# 05_AUDIO.net
KiCad netlist of a schematic drawn in Altium Designer
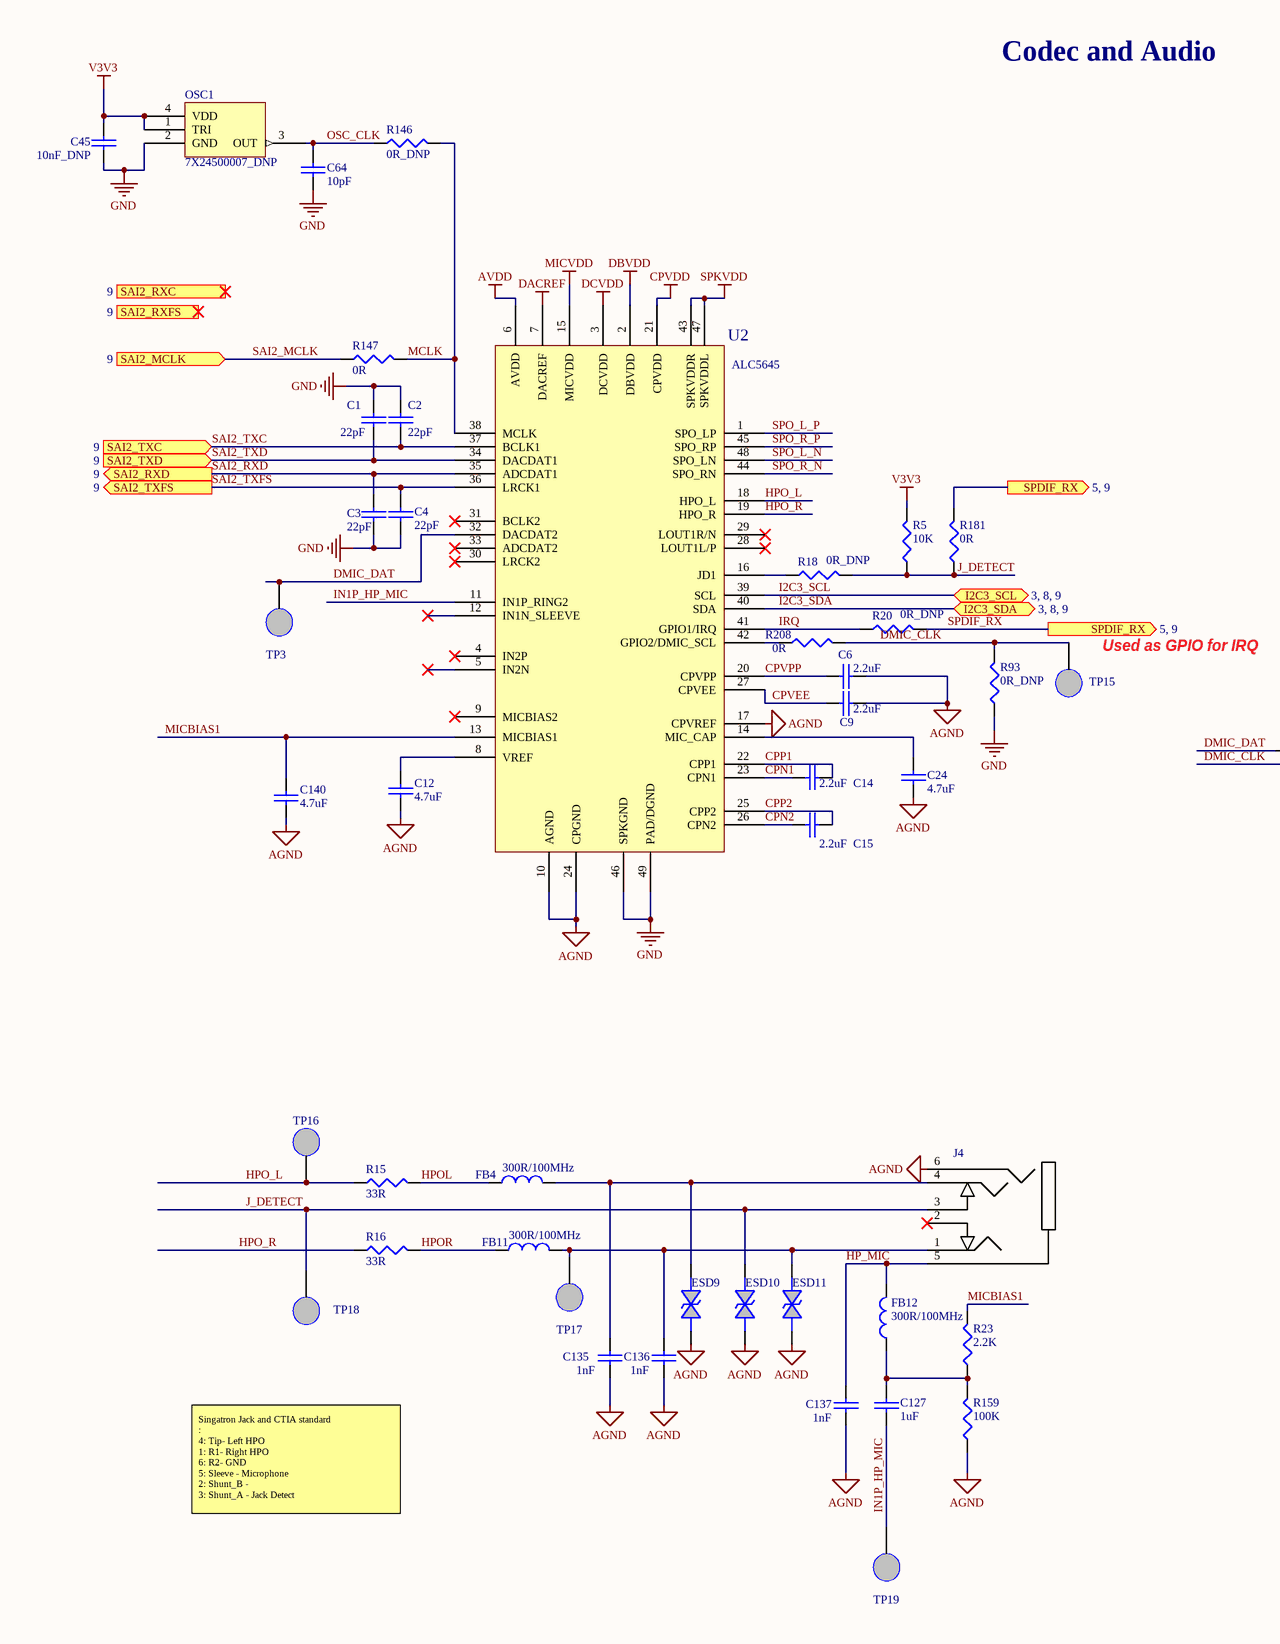
[diagram p0: 05_AUDIO.SchDoc, left]
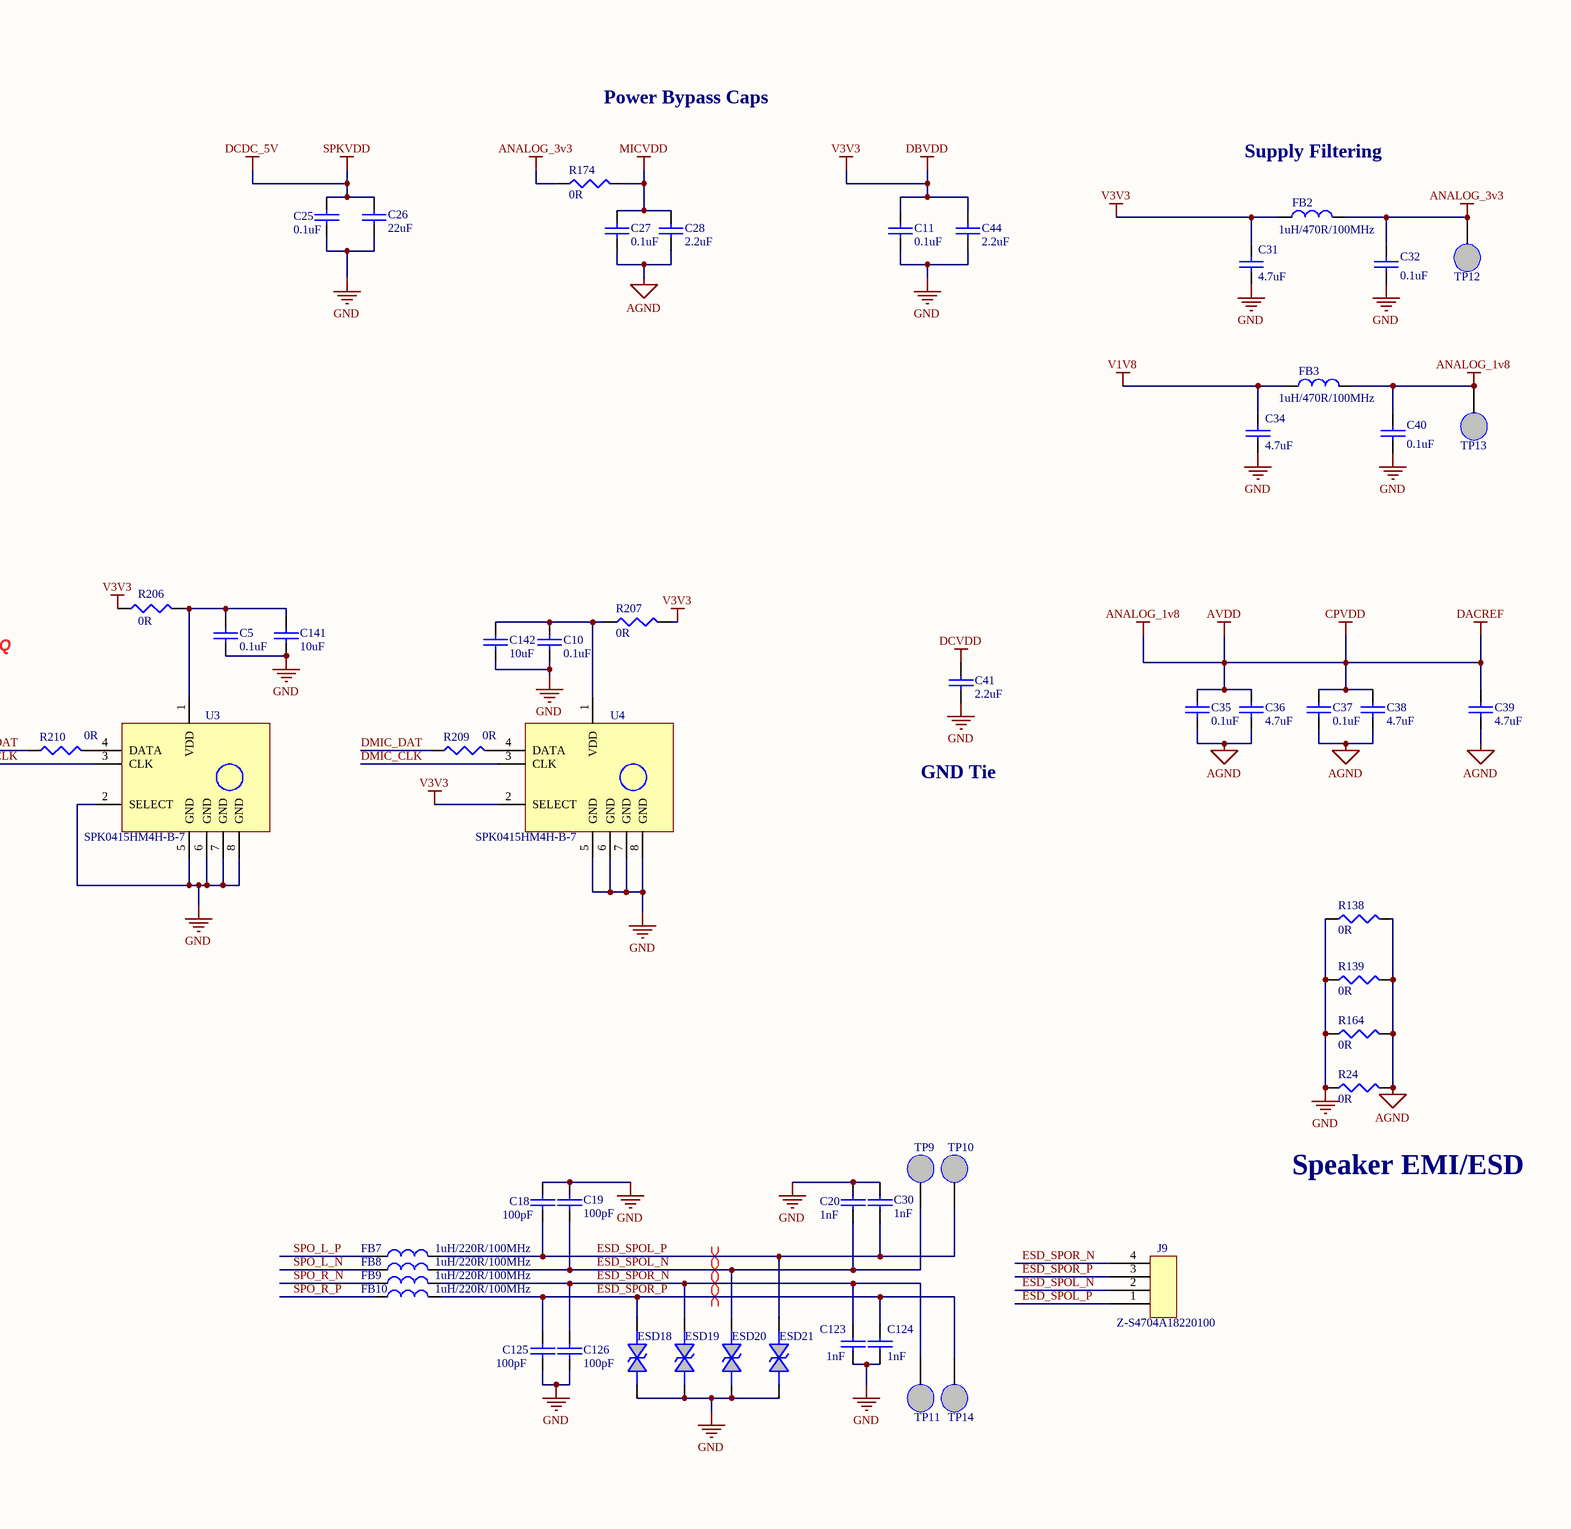
[diagram p1: 05_AUDIO.SchDoc, right]

(export (version "E")
  (design (tool "Eeschema 10.0.6"))
  (components
    (comp (ref "C1")
      (value "22pF")
      (footprint "0201")
      (description "CAP CER 22pF 6.3V 2% C0G NP0 0201")
      (fields (field (name "MPN") "GJM0335C0J220GB01D") (field (name "Comment") "22pF/6.3V"))
      (libsource (lib "links") (part "CAP_0201_22pF"))
    )
    (comp (ref "C2")
      (value "22pF")
      (footprint "0201")
      (description "CAP CER 22pF 6.3V 2% C0G NP0 0201")
      (fields (field (name "MPN") "GJM0335C0J220GB01D") (field (name "Comment") "22pF/6.3V"))
      (libsource (lib "links") (part "CAP_0201_22pF"))
    )
    (comp (ref "C3")
      (value "22pF")
      (footprint "0201")
      (description "CAP CER 22pF 6.3V 2% C0G NP0 0201")
      (fields (field (name "MPN") "GJM0335C0J220GB01D") (field (name "Comment") "22pF/6.3V"))
      (libsource (lib "links") (part "CAP_0201_22pF"))
    )
    (comp (ref "C4")
      (value "22pF")
      (footprint "0201")
      (description "CAP CER 22pF 6.3V 2% C0G NP0 0201")
      (fields (field (name "MPN") "GJM0335C0J220GB01D") (field (name "Comment") "22pF/6.3V"))
      (libsource (lib "links") (part "CAP_0201_22pF"))
    )
    (comp (ref "C5")
      (value "0.1uF")
      (footprint "0201")
      (description "CAP CER 0.1UF 10V 10% X5R 0201")
      (fields (field (name "MPN") "C0603X5R1A104K030BC") (field (name "Comment") "0.1uF/10V"))
      (libsource (lib "links") (part "CAP_0201_0.1uF"))
    )
    (comp (ref "C6")
      (value "2.2uF")
      (footprint "0201")
      (description "CAP CER 2.2uF 6.3V 20% X5R 0201")
      (fields (field (name "MPN") "GRM033R60J225ME15D") (field (name "Comment") "2.2uF/6.3V"))
      (libsource (lib "links") (part "CAP_0201_2.2uF"))
    )
    (comp (ref "C9")
      (value "2.2uF")
      (footprint "0201")
      (description "CAP CER 2.2uF 6.3V 20% X5R 0201")
      (fields (field (name "MPN") "GRM033R60J225ME15D") (field (name "Comment") "2.2uF/6.3V"))
      (libsource (lib "links") (part "CAP_0201_2.2uF"))
    )
    (comp (ref "C10")
      (value "0.1uF")
      (footprint "0201")
      (description "CAP CER 0.1UF 10V 10% X5R 0201")
      (fields (field (name "MPN") "C0603X5R1A104K030BC") (field (name "Comment") "0.1uF/10V"))
      (libsource (lib "links") (part "CAP_0201_0.1uF"))
    )
    (comp (ref "C11")
      (value "0.1uF")
      (footprint "0201")
      (description "CAP CER 0.1UF 10V 10% X5R 0201")
      (fields (field (name "MPN") "C0603X5R1A104K030BC") (field (name "Comment") "0.1uF/10V"))
      (libsource (lib "links") (part "CAP_0201_0.1uF"))
    )
    (comp (ref "C12")
      (value "4.7uF")
      (footprint "0402")
      (description "CAP CER 4.7UF 10V 20% X5R 0402")
      (fields (field (name "MPN") "C1005X5R1A475M050BC") (field (name "Comment") "4.7uF/10V"))
      (libsource (lib "links") (part "CAP_0201_4.7uF"))
    )
    (comp (ref "C14")
      (value "2.2uF")
      (footprint "0201")
      (description "CAP CER 2.2uF 6.3V 20% X5R 0201")
      (fields (field (name "MPN") "GRM033R60J225ME15D") (field (name "Comment") "2.2uF/6.3V"))
      (libsource (lib "links") (part "CAP_0201_2.2uF"))
    )
    (comp (ref "C15")
      (value "2.2uF")
      (footprint "0201")
      (description "CAP CER 2.2uF 6.3V 20% X5R 0201")
      (fields (field (name "MPN") "GRM033R60J225ME15D") (field (name "Comment") "2.2uF/6.3V"))
      (libsource (lib "links") (part "CAP_0201_2.2uF"))
    )
    (comp (ref "C18")
      (value "100pF")
      (footprint "0201")
      (description "CAP CER 100PF 25V X7R 0201")
      (fields (field (name "MPN") "GRM033R71E101KA01D") (field (name "Comment") "100pF/25V"))
      (libsource (lib "links") (part "CAP_0201_100pF"))
    )
    (comp (ref "C19")
      (value "100pF")
      (footprint "0201")
      (description "CAP CER 100PF 25V X7R 0201")
      (fields (field (name "MPN") "GRM033R71E101KA01D") (field (name "Comment") "100pF/25V"))
      (libsource (lib "links") (part "CAP_0201_100pF"))
    )
    (comp (ref "C20")
      (value "1nF")
      (footprint "0201")
      (description "CAP CER 1nF 25V 10% X7R 0201")
      (fields (field (name "MPN") "GRM033R71E102KA01D") (field (name "Comment") "1nF/25V"))
      (libsource (lib "links") (part "CAP_0201_1.0nF"))
    )
    (comp (ref "C24")
      (value "4.7uF")
      (footprint "0402")
      (description "CAP CER 4.7UF 10V 20% X5R 0402")
      (fields (field (name "MPN") "C1005X5R1A475M050BC") (field (name "Comment") "4.7uF/10V"))
      (libsource (lib "links") (part "CAP_0201_4.7uF"))
    )
    (comp (ref "C25")
      (value "0.1uF")
      (footprint "0402")
      (description "CAP CER 0.1uF 16V 10% X7R 0402")
      (fields (field (name "MPN") "C0402C104K4RACTU") (field (name "Comment") "0.1uF/16V"))
      (libsource (lib "links") (part "CAP_0402_0.1uF"))
    )
    (comp (ref "C26")
      (value "22uF")
      (footprint "0603")
      (description "CAP CER 22UF 6.3V 10% X5R 0603")
      (fields (field (name "MPN") "CL10A226KQ8NRNE") (field (name "Comment") "10uF/10V"))
      (libsource (lib "links") (part "CAP_0603_22uF"))
    )
    (comp (ref "C27")
      (value "0.1uF")
      (footprint "0201")
      (description "CAP CER 0.1UF 10V 10% X5R 0201")
      (fields (field (name "MPN") "C0603X5R1A104K030BC") (field (name "Comment") "0.1uF/10V"))
      (libsource (lib "links") (part "CAP_0201_0.1uF"))
    )
    (comp (ref "C28")
      (value "2.2uF")
      (footprint "0201")
      (description "CAP CER 2.2uF 6.3V 20% X5R 0201")
      (fields (field (name "MPN") "GRM033R60J225ME15D") (field (name "Comment") "2.2uF/6.3V"))
      (libsource (lib "links") (part "CAP_0201_2.2uF"))
    )
    (comp (ref "C30")
      (value "1nF")
      (footprint "0201")
      (description "CAP CER 1nF 25V 10% X7R 0201")
      (fields (field (name "MPN") "GRM033R71E102KA01D") (field (name "Comment") "1nF/25V"))
      (libsource (lib "links") (part "CAP_0201_1.0nF"))
    )
    (comp (ref "C31")
      (value "4.7uF")
      (footprint "0402")
      (description "CAP CER 4.7UF 10V 20% X5R 0402")
      (fields (field (name "MPN") "C1005X5R1A475M050BC") (field (name "Comment") "4.7uF/10V"))
      (libsource (lib "links") (part "CAP_0402_4.7uF"))
    )
    (comp (ref "C32")
      (value "0.1uF")
      (footprint "0603")
      (description "CAP CER 0.1UF 10V 10% X5R 0603")
      (fields (field (name "MPN") "GRM188R71C104M") (field (name "Comment") "0.1uF/10V"))
      (libsource (lib "links") (part "CAP_0603_0.1uF"))
    )
    (comp (ref "C34")
      (value "4.7uF")
      (footprint "0402")
      (description "CAP CER 4.7UF 10V 20% X5R 0402")
      (fields (field (name "MPN") "C1005X5R1A475M050BC") (field (name "Comment") "4.7uF/10V"))
      (libsource (lib "links") (part "CAP_0402_4.7uF"))
    )
    (comp (ref "C35")
      (value "0.1uF")
      (footprint "0201")
      (description "CAP CER 0.1UF 10V 10% X5R 0201")
      (fields (field (name "MPN") "C0603X5R1A104K030BC") (field (name "Comment") "0.1uF/10V"))
      (libsource (lib "links") (part "CAP_0201_0.1uF"))
    )
    (comp (ref "C36")
      (value "4.7uF")
      (footprint "0402")
      (description "CAP CER 4.7UF 10V 20% X5R 0402")
      (fields (field (name "MPN") "C1005X5R1A475M050BC") (field (name "Comment") "4.7uF/10V"))
      (libsource (lib "links") (part "CAP_0201_4.7uF"))
    )
    (comp (ref "C37")
      (value "0.1uF")
      (footprint "0201")
      (description "CAP CER 0.1UF 10V 10% X5R 0201")
      (fields (field (name "MPN") "C0603X5R1A104K030BC") (field (name "Comment") "0.1uF/10V"))
      (libsource (lib "links") (part "CAP_0201_0.1uF"))
    )
    (comp (ref "C38")
      (value "4.7uF")
      (footprint "0402")
      (description "CAP CER 4.7UF 10V 20% X5R 0402")
      (fields (field (name "MPN") "C1005X5R1A475M050BC") (field (name "Comment") "4.7uF/10V"))
      (libsource (lib "links") (part "CAP_0201_4.7uF"))
    )
    (comp (ref "C39")
      (value "4.7uF")
      (footprint "0402")
      (description "CAP CER 4.7UF 10V 20% X5R 0402")
      (fields (field (name "MPN") "C1005X5R1A475M050BC") (field (name "Comment") "4.7uF/10V"))
      (libsource (lib "links") (part "CAP_0201_4.7uF"))
    )
    (comp (ref "C40")
      (value "0.1uF")
      (footprint "0402")
      (description "CAP CER 0.1uF 16V 10% X7R 0402")
      (fields (field (name "MPN") "C0402C104K4RACTU") (field (name "Comment") "0.1uF/16V"))
      (libsource (lib "links") (part "CAP_0402_0.1uF"))
    )
    (comp (ref "C41")
      (value "2.2uF")
      (footprint "0201")
      (description "CAP CER 2.2uF 6.3V 20% X5R 0201")
      (fields (field (name "MPN") "GRM033R60J225ME15D") (field (name "Comment") "2.2uF/6.3V"))
      (libsource (lib "links") (part "CAP_0201_2.2uF"))
    )
    (comp (ref "C44")
      (value "2.2uF")
      (footprint "0201")
      (description "CAP CER 2.2uF 6.3V 20% X5R 0201")
      (fields (field (name "MPN") "GRM033R60J225ME15D") (field (name "Comment") "2.2uF/6.3V"))
      (libsource (lib "links") (part "CAP_0201_2.2uF"))
    )
    (comp (ref "C45")
      (value "10nF_DNP")
      (footprint "0201")
      (description "CAP CER 0.01UF 10V 10% X5R 0201")
      (fields (field (name "MPN") "GRM033R61A103KA01D"))
      (libsource (lib "links") (part "CAP_0201_10nF"))
    )
    (comp (ref "C64")
      (value "10pF")
      (footprint "0201")
      (description "CAP CER 10PF 25V 5% C0H 0201")
      (fields (field (name "MPN") "GJM0336C1E100JB01D") (field (name "Comment") "10pF/25V"))
      (libsource (lib "links") (part "CAP_0201_10pF_HF"))
    )
    (comp (ref "C123")
      (value "1nF")
      (footprint "0201")
      (description "CAP CER 1nF 25V 10% X7R 0201")
      (fields (field (name "MPN") "GRM033R71E102KA01D") (field (name "Comment") "1nF/25V"))
      (libsource (lib "links") (part "CAP_0201_1.0nF"))
    )
    (comp (ref "C124")
      (value "1nF")
      (footprint "0201")
      (description "CAP CER 1nF 25V 10% X7R 0201")
      (fields (field (name "MPN") "GRM033R71E102KA01D") (field (name "Comment") "1nF/25V"))
      (libsource (lib "links") (part "CAP_0201_1.0nF"))
    )
    (comp (ref "C125")
      (value "100pF")
      (footprint "0201")
      (description "CAP CER 100PF 25V X7R 0201")
      (fields (field (name "MPN") "GRM033R71E101KA01D") (field (name "Comment") "100pF/25V"))
      (libsource (lib "links") (part "CAP_0201_100pF"))
    )
    (comp (ref "C126")
      (value "100pF")
      (footprint "0201")
      (description "CAP CER 100PF 25V X7R 0201")
      (fields (field (name "MPN") "GRM033R71E101KA01D") (field (name "Comment") "100pF/25V"))
      (libsource (lib "links") (part "CAP_0201_100pF"))
    )
    (comp (ref "C127")
      (value "1uF")
      (footprint "0402")
      (description "CAP CER 1.0UF 6.3V 10% X5R 0402")
      (fields (field (name "MPN") "C0603X5R0J105M030BC") (field (name "Comment") "1uF/6.3V"))
      (libsource (lib "links") (part "CAP_0402_1.0uF"))
    )
    (comp (ref "C135")
      (value "1nF")
      (footprint "0201")
      (description "CAP CER 1nF 25V 10% X7R 0201")
      (fields (field (name "MPN") "GRM033R71E102KA01D") (field (name "Comment") "1nF/25V"))
      (libsource (lib "links") (part "CAP_0201_1.0nF"))
    )
    (comp (ref "C136")
      (value "1nF")
      (footprint "0201")
      (description "CAP CER 1nF 25V 10% X7R 0201")
      (fields (field (name "MPN") "GRM033R71E102KA01D") (field (name "Comment") "1nF/25V"))
      (libsource (lib "links") (part "CAP_0201_1.0nF"))
    )
    (comp (ref "C137")
      (value "1nF")
      (footprint "0201")
      (description "CAP CER 1nF 25V 10% X7R 0201")
      (fields (field (name "MPN") "GRM033R71E102KA01D") (field (name "Comment") "1nF/25V"))
      (libsource (lib "links") (part "CAP_0201_1.0nF"))
    )
    (comp (ref "C140")
      (value "4.7uF")
      (footprint "0402")
      (description "CAP CER 4.7UF 10V 20% X5R 0402")
      (fields (field (name "MPN") "C1005X5R1A475M050BC") (field (name "Comment") "4.7uF/10V"))
      (libsource (lib "links") (part "CAP_0201_4.7uF"))
    )
    (comp (ref "C141")
      (value "10uF")
      (footprint "0402")
      (description "CAP CER 10UF 10V 20% X5R 0402")
      (fields (field (name "MPN") "CL05A106MP5NUNC") (field (name "Comment") "10uF/10V"))
      (libsource (lib "links") (part "CAP_0402_10uF"))
    )
    (comp (ref "C142")
      (value "10uF")
      (footprint "0402")
      (description "CAP CER 10UF 10V 20% X5R 0402")
      (fields (field (name "MPN") "CL05A106MP5NUNC") (field (name "Comment") "10uF/10V"))
      (libsource (lib "links") (part "CAP_0402_10uF"))
    )
    (comp (ref "ESD9")
      (value "3.5pF/5V")
      (footprint "0201")
      (description "DIODE TVS 15kV 10V 50A 8pF SMT RoHS")
      (fields (field (name "MPN") "DESD5V0V1BCSP-7"))
      (libsource (lib "links") (part "DIODE BI-DIR TRIG"))
    )
    (comp (ref "ESD10")
      (value "3.5pF/5V")
      (footprint "0201")
      (description "DIODE TVS 15kV 10V 50A 8pF SMT RoHS")
      (fields (field (name "MPN") "DESD5V0V1BCSP-7"))
      (libsource (lib "links") (part "DIODE BI-DIR TRIG"))
    )
    (comp (ref "ESD11")
      (value "3.5pF/5V")
      (footprint "0201")
      (description "DIODE TVS 15kV 10V 50A 8pF SMT RoHS")
      (fields (field (name "MPN") "DESD5V0V1BCSP-7"))
      (libsource (lib "links") (part "DIODE BI-DIR TRIG"))
    )
    (comp (ref "ESD18")
      (value "3.5pF/5V")
      (footprint "0201")
      (description "DIODE TVS 15kV 10V 50A 8pF SMT RoHS")
      (fields (field (name "MPN") "DESD5V0V1BCSP-7"))
      (libsource (lib "links") (part "DIODE BI-DIR TRIG"))
    )
    (comp (ref "ESD19")
      (value "3.5pF/5V")
      (footprint "0201")
      (description "DIODE TVS 15kV 10V 50A 8pF SMT RoHS")
      (fields (field (name "MPN") "DESD5V0V1BCSP-7"))
      (libsource (lib "links") (part "DIODE BI-DIR TRIG"))
    )
    (comp (ref "ESD20")
      (value "3.5pF/5V")
      (footprint "0201")
      (description "DIODE TVS 15kV 10V 50A 8pF SMT RoHS")
      (fields (field (name "MPN") "DESD5V0V1BCSP-7"))
      (libsource (lib "links") (part "DIODE BI-DIR TRIG"))
    )
    (comp (ref "ESD21")
      (value "3.5pF/5V")
      (footprint "0201")
      (description "DIODE TVS 15kV 10V 50A 8pF SMT RoHS")
      (fields (field (name "MPN") "DESD5V0V1BCSP-7"))
      (libsource (lib "links") (part "DIODE BI-DIR TRIG"))
    )
    (comp (ref "FB2")
      (value "1uH/470R/100MHz")
      (footprint "0603")
      (description "FERRITE CHIP 470 OHM 1.0A 0603")
      (fields (field (name "MPN") "BLM18PG471SN1"))
      (libsource (lib "SpacePark") (part "INDUCTOR_BLM18PG471SN1"))
    )
    (comp (ref "FB3")
      (value "1uH/470R/100MHz")
      (footprint "0603")
      (description "FERRITE CHIP 470 OHM 1.0A 0603")
      (fields (field (name "MPN") "BLM18PG471SN1"))
      (libsource (lib "SpacePark") (part "INDUCTOR_BLM18PG471SN1"))
    )
    (comp (ref "FB4")
      (value "300R/100MHz")
      (footprint "0402")
      (description "EMI FILTER FCM1005KF-301T03 (300,300MA)")
      (fields (field (name "MPN") "FCM1005KF-301T03"))
      (libsource (lib "SpacePark") (part "INDUCTOR_BLM18EG221SN1D"))
    )
    (comp (ref "FB7")
      (value "1uH/220R/100MHz")
      (footprint "0603")
      (description "FERRITE CHIP 220 OHM 2.0A 0603")
      (fields (field (name "MPN") "BLM18EG221SN1D"))
      (libsource (lib "SpacePark") (part "INDUCTOR_BLM18EG221SN1D"))
    )
    (comp (ref "FB8")
      (value "1uH/220R/100MHz")
      (footprint "0603")
      (description "FERRITE CHIP 220 OHM 2.0A 0603")
      (fields (field (name "MPN") "BLM18EG221SN1D"))
      (libsource (lib "SpacePark") (part "INDUCTOR_BLM18EG221SN1D"))
    )
    (comp (ref "FB9")
      (value "1uH/220R/100MHz")
      (footprint "0603")
      (description "FERRITE CHIP 220 OHM 2.0A 0603")
      (fields (field (name "MPN") "BLM18EG221SN1D"))
      (libsource (lib "SpacePark") (part "INDUCTOR_BLM18EG221SN1D"))
    )
    (comp (ref "FB10")
      (value "1uH/220R/100MHz")
      (footprint "0603")
      (description "FERRITE CHIP 220 OHM 2.0A 0603")
      (fields (field (name "MPN") "BLM18EG221SN1D"))
      (libsource (lib "SpacePark") (part "INDUCTOR_BLM18EG221SN1D"))
    )
    (comp (ref "FB11")
      (value "300R/100MHz")
      (footprint "0402")
      (description "EMI FILTER FCM1005KF-301T03 (300,300MA)")
      (fields (field (name "MPN") "FCM1005KF-301T03"))
      (libsource (lib "SpacePark") (part "INDUCTOR_BLM18EG221SN1D"))
    )
    (comp (ref "FB12")
      (value "300R/100MHz")
      (footprint "0402")
      (description "EMI FILTER FCM1005KF-301T03 (300,300MA)")
      (fields (field (name "MPN") "FCM1005KF-301T03"))
      (libsource (lib "SpacePark") (part "INDUCTOR_BLM18EG221SN1D"))
    )
    (comp (ref "J4")
      (value "CONN_2SJ2296-000111")
      (footprint "AUDIO-2SJ2296-000111")
      (description "CONN AUDIO JACK 3.5MM 6COND SMD")
      (fields (field (name "MPN") "2SJ2296-000111"))
      (libsource (lib "SpacePark") (part "CONN_2SJ2296-000111"))
    )
    (comp (ref "J9")
      (value "Z-S4704A18220100")
      (footprint "SIP4-2_54-S4704A18220100")
      (description "CONN TERM BLOCK 2.54MM 4POS PCB")
      (libsource (lib "SpacePark") (part "CONN_TERMINAL_4POS_PHOENIX"))
    )
    (comp (ref "OSC1")
      (value "7X24500007_DNP")
      (footprint "4-SMD-OSC")
      (description "24.576MHz SINE Oscillator Surface Mount 3.3V 13mA Enable/Disable")
      (libsource (lib "SpacePark") (part "OSC_7X24500007"))
    )
    (comp (ref "R5")
      (value "10K")
      (footprint "0201")
      (description "RES SMD 10K OHM JUMPER 1/20W  0201")
      (fields (field (name "MPN") "ERJ-1GEF103C"))
      (libsource (lib "links") (part "R_0201_10K"))
    )
    (comp (ref "R15")
      (value "33R")
      (footprint "0402")
      (description "RES SMD 33 OHM 1% 1/10W 0402")
      (fields (field (name "MPN") "RC0402FR-0733R"))
      (libsource (lib "links") (part "R_0402_33"))
    )
    (comp (ref "R16")
      (value "33R")
      (footprint "0402")
      (description "RES SMD 33 OHM 1% 1/10W 0402")
      (fields (field (name "MPN") "RC0402FR-0733R"))
      (libsource (lib "links") (part "R_0402_33"))
    )
    (comp (ref "R18")
      (value "0R_DNP")
      (footprint "0201")
      (description "RES SMD 0.0OHM JUMPER 1/20W 0201")
      (fields (field (name "MPN") "ERJ-1GN0R00C"))
      (libsource (lib "links") (part "R_0201_0"))
    )
    (comp (ref "R20")
      (value "0R_DNP")
      (footprint "0201")
      (description "RES SMD 0.0OHM JUMPER 1/20W 0201")
      (fields (field (name "MPN") "ERJ-1GN0R00C"))
      (libsource (lib "links") (part "R_0201_0"))
    )
    (comp (ref "R23")
      (value "2.2K")
      (footprint "0201")
      (description "RES SMD 2.2K OHM 1% 1/20W 0201")
      (fields (field (name "MPN") "ERJ-1GEF2201C"))
      (libsource (lib "links") (part "R_0201_2.2K"))
    )
    (comp (ref "R24")
      (value "0R")
      (footprint "0201")
      (description "RES SMD 0.0OHM JUMPER 1/20W 0201")
      (fields (field (name "MPN") "ERJ-1GN0R00C"))
      (libsource (lib "links") (part "R_0805_0"))
    )
    (comp (ref "R93")
      (value "0R_DNP")
      (footprint "0201")
      (description "RES SMD 0.0OHM JUMPER 1/20W 0201")
      (fields (field (name "MPN") "ERJ-1GN0R00C"))
      (libsource (lib "links") (part "R_0201_0"))
    )
    (comp (ref "R138")
      (value "0R")
      (footprint "0201")
      (description "RES SMD 0.0OHM JUMPER 1/20W 0201")
      (fields (field (name "MPN") "ERJ-1GN0R00C"))
      (libsource (lib "links") (part "R_0805_0"))
    )
    (comp (ref "R139")
      (value "0R")
      (footprint "0201")
      (description "RES SMD 0.0OHM JUMPER 1/20W 0201")
      (fields (field (name "MPN") "ERJ-1GN0R00C"))
      (libsource (lib "links") (part "R_0805_0"))
    )
    (comp (ref "R146")
      (value "0R_DNP")
      (footprint "0201")
      (description "RES SMD 0.0OHM JUMPER 1/20W 0201")
      (fields (field (name "MPN") "ERJ-1GN0R00C"))
      (libsource (lib "links") (part "R_0201_0"))
    )
    (comp (ref "R147")
      (value "0R")
      (footprint "0201")
      (description "RES SMD 0.0OHM JUMPER 1/20W 0201")
      (fields (field (name "MPN") "ERJ-1GN0R00C"))
      (libsource (lib "links") (part "R_0201_0"))
    )
    (comp (ref "R159")
      (value "100K")
      (footprint "0402")
      (description "RES CHIP 100K 1/16W 5%(0402)")
      (fields (field (name "MPN") "YAG3045TR-ND"))
      (libsource (lib "links") (part "R_0402_1.6k"))
    )
    (comp (ref "R164")
      (value "0R")
      (footprint "0201")
      (description "RES SMD 0.0OHM JUMPER 1/20W 0201")
      (fields (field (name "MPN") "ERJ-1GN0R00C"))
      (libsource (lib "links") (part "R_0805_0"))
    )
    (comp (ref "R174")
      (value "0R")
      (footprint "0402")
      (description "RES SMD 0.0 OHM JUMPER 1/10W  0402")
      (fields (field (name "MPN") "ERJ-2GE0R00X"))
      (libsource (lib "links") (part "R_0402_0"))
    )
    (comp (ref "R181")
      (value "0R")
      (footprint "0201")
      (description "RES SMD 0.0OHM JUMPER 1/20W 0201")
      (fields (field (name "MPN") "ERJ-1GN0R00C"))
      (libsource (lib "links") (part "R_0201_0"))
    )
    (comp (ref "R206")
      (value "0R")
      (footprint "0201")
      (description "RES SMD 0.0OHM JUMPER 1/20W 0201")
      (fields (field (name "MPN") "ERJ-1GN0R00C"))
      (libsource (lib "links") (part "R_0805_0"))
    )
    (comp (ref "R207")
      (value "0R")
      (footprint "0201")
      (description "RES SMD 0.0OHM JUMPER 1/20W 0201")
      (fields (field (name "MPN") "ERJ-1GN0R00C"))
      (libsource (lib "links") (part "R_0805_0"))
    )
    (comp (ref "R208")
      (value "0R")
      (footprint "0201")
      (description "RES SMD 0.0OHM JUMPER 1/20W 0201")
      (fields (field (name "MPN") "ERJ-1GN0R00C"))
      (libsource (lib "links") (part "R_0805_0"))
    )
    (comp (ref "R209")
      (value "0R")
      (footprint "0201")
      (description "RES SMD 0.0OHM JUMPER 1/20W 0201")
      (fields (field (name "MPN") "ERJ-1GN0R00C"))
      (libsource (lib "links") (part "R_0805_0"))
    )
    (comp (ref "R210")
      (value "0R")
      (footprint "0201")
      (description "RES SMD 0.0OHM JUMPER 1/20W 0201")
      (fields (field (name "MPN") "ERJ-1GN0R00C"))
      (libsource (lib "links") (part "R_0805_0"))
    )
    (comp (ref "TP3")
      (value "TP NM")
      (footprint "TP_SMD")
      (description "TEST POIN")
      (libsource (lib "links") (part "TP"))
    )
    (comp (ref "TP9")
      (value "TP NM")
      (footprint "TP_SMD")
      (description "TEST POIN")
      (libsource (lib "links") (part "TP"))
    )
    (comp (ref "TP10")
      (value "TP NM")
      (footprint "TP_SMD")
      (description "TEST POIN")
      (libsource (lib "links") (part "TP"))
    )
    (comp (ref "TP11")
      (value "TP NM")
      (footprint "TP_SMD")
      (description "TEST POIN")
      (libsource (lib "links") (part "TP"))
    )
    (comp (ref "TP12")
      (value "TP NM")
      (footprint "TP_SMD")
      (description "TEST POIN")
      (libsource (lib "links") (part "TP"))
    )
    (comp (ref "TP13")
      (value "TP NM")
      (footprint "TP_SMD")
      (description "TEST POIN")
      (libsource (lib "links") (part "TP"))
    )
    (comp (ref "TP14")
      (value "TP NM")
      (footprint "TP_SMD")
      (description "TEST POIN")
      (libsource (lib "links") (part "TP"))
    )
    (comp (ref "TP15")
      (value "TP NM")
      (footprint "TP_SMD")
      (description "TEST POIN")
      (libsource (lib "links") (part "TP"))
    )
    (comp (ref "TP16")
      (value "TP NM")
      (footprint "TP_SMD")
      (description "TEST POIN")
      (libsource (lib "links") (part "TP"))
    )
    (comp (ref "TP17")
      (value "TP NM")
      (footprint "TP_SMD")
      (description "TEST POIN")
      (libsource (lib "links") (part "TP"))
    )
    (comp (ref "TP18")
      (value "TP NM")
      (footprint "TP_SMD")
      (description "TEST POIN")
      (libsource (lib "links") (part "TP"))
    )
    (comp (ref "TP19")
      (value "TP NM")
      (footprint "TP_SMD")
      (description "TEST POIN")
      (libsource (lib "links") (part "TP"))
    )
    (comp (ref "U2")
      (value "ALC5645")
      (footprint "CODEC_ALC5645")
      (description "Multi-Channel Audio Hub/CODEC and SounzReal Digital Sound Effect")
      (libsource (lib "SpacePark") (part "ALC5645"))
    )
    (comp (ref "U3")
      (value "SPK0415HM4H-B-7")
      (footprint "Microphone_SPK0415HM4H-B-7")
      (description "Microphone MEMS, Digital PDM OMNI -26dB")
      (libsource (lib "SpacePark") (part "Microphone_SPK0415HM4H-B-7"))
    )
    (comp (ref "U4")
      (value "SPK0415HM4H-B-7")
      (footprint "Microphone_SPK0415HM4H-B-7")
      (description "Microphone MEMS, Digital PDM OMNI -26dB")
      (libsource (lib "SpacePark") (part "Microphone_SPK0415HM4H-B-7"))
    )
  )
  (nets
    (net (code "1") (name "/CPN1") (class "Default")
      (node (ref "C14") (pin "1") (pinfunction "1_1") (pintype "passive"))
      (node (ref "U2") (pin "23") (pinfunction "CPN1_23") (pintype "passive"))
    )
    (net (code "2") (name "/CPN2") (class "Default")
      (node (ref "C15") (pin "1") (pinfunction "1_1") (pintype "passive"))
      (node (ref "U2") (pin "26") (pinfunction "CPN2_26") (pintype "passive"))
    )
    (net (code "3") (name "/CPP1") (class "Default")
      (node (ref "C14") (pin "2") (pinfunction "2_2") (pintype "passive"))
      (node (ref "U2") (pin "22") (pinfunction "CPP1_22") (pintype "passive"))
    )
    (net (code "4") (name "/CPP2") (class "Default")
      (node (ref "C15") (pin "2") (pinfunction "2_2") (pintype "passive"))
      (node (ref "U2") (pin "25") (pinfunction "CPP2_25") (pintype "passive"))
    )
    (net (code "5") (name "/CPVEE") (class "Default")
      (node (ref "C9") (pin "1") (pinfunction "1_1") (pintype "passive"))
      (node (ref "U2") (pin "27") (pinfunction "CPVEE_27") (pintype "passive"))
    )
    (net (code "6") (name "/CPVPP") (class "Default")
      (node (ref "C6") (pin "1") (pinfunction "1_1") (pintype "passive"))
      (node (ref "U2") (pin "20") (pinfunction "CPVPP_20") (pintype "passive"))
    )
    (net (code "7") (name "/DMIC_CLK") (class "Default")
      (node (ref "R208") (pin "2") (pintype "passive"))
      (node (ref "R93") (pin "2") (pintype "passive"))
      (node (ref "TP15") (pin "1") (pinfunction "1_1") (pintype "passive"))
      (node (ref "U3") (pin "3") (pinfunction "CLK_3") (pintype "passive"))
      (node (ref "U4") (pin "3") (pinfunction "CLK_3") (pintype "passive"))
    )
    (net (code "8") (name "/DMIC_DAT") (class "Default")
      (node (ref "R209") (pin "1") (pintype "passive"))
      (node (ref "R210") (pin "1") (pintype "passive"))
      (node (ref "TP3") (pin "1") (pinfunction "1_1") (pintype "passive"))
      (node (ref "U2") (pin "32") (pinfunction "DACDAT2_32") (pintype "passive"))
    )
    (net (code "9") (name "/ESD_SPOL_N") (class "Default")
      (node (ref "C19") (pin "2") (pinfunction "2_2") (pintype "passive"))
      (node (ref "C20") (pin "1") (pinfunction "1_1") (pintype "passive"))
      (node (ref "ESD20") (pin "2") (pinfunction "2_2") (pintype "passive"))
      (node (ref "FB8") (pin "2") (pinfunction "2_2") (pintype "passive"))
      (node (ref "J9") (pin "2") (pinfunction "2_2") (pintype "passive"))
      (node (ref "TP9") (pin "1") (pinfunction "1_1") (pintype "passive"))
    )
    (net (code "10") (name "/ESD_SPOL_P") (class "Default")
      (node (ref "C18") (pin "2") (pinfunction "2_2") (pintype "passive"))
      (node (ref "C30") (pin "1") (pinfunction "1_1") (pintype "passive"))
      (node (ref "ESD21") (pin "2") (pinfunction "2_2") (pintype "passive"))
      (node (ref "FB7") (pin "2") (pinfunction "2_2") (pintype "passive"))
      (node (ref "J9") (pin "1") (pinfunction "1_1") (pintype "passive"))
      (node (ref "TP10") (pin "1") (pinfunction "1_1") (pintype "passive"))
    )
    (net (code "11") (name "/ESD_SPOR_N") (class "Default")
      (node (ref "C123") (pin "2") (pinfunction "2_2") (pintype "passive"))
      (node (ref "C126") (pin "1") (pinfunction "1_1") (pintype "passive"))
      (node (ref "ESD19") (pin "2") (pinfunction "2_2") (pintype "passive"))
      (node (ref "FB9") (pin "2") (pinfunction "2_2") (pintype "passive"))
      (node (ref "J9") (pin "4") (pinfunction "4_4") (pintype "passive"))
      (node (ref "TP11") (pin "1") (pinfunction "1_1") (pintype "passive"))
    )
    (net (code "12") (name "/ESD_SPOR_P") (class "Default")
      (node (ref "C124") (pin "2") (pinfunction "2_2") (pintype "passive"))
      (node (ref "C125") (pin "1") (pinfunction "1_1") (pintype "passive"))
      (node (ref "ESD18") (pin "2") (pinfunction "2_2") (pintype "passive"))
      (node (ref "FB10") (pin "2") (pinfunction "2_2") (pintype "passive"))
      (node (ref "J9") (pin "3") (pinfunction "3_3") (pintype "passive"))
      (node (ref "TP14") (pin "1") (pinfunction "1_1") (pintype "passive"))
    )
    (net (code "13") (name "/HPOL") (class "Default")
      (node (ref "FB4") (pin "1") (pinfunction "1_1") (pintype "passive"))
      (node (ref "R15") (pin "2") (pintype "passive"))
    )
    (net (code "14") (name "/HPOR") (class "Default")
      (node (ref "FB11") (pin "1") (pinfunction "1_1") (pintype "passive"))
      (node (ref "R16") (pin "2") (pintype "passive"))
    )
    (net (code "15") (name "/HPO_L") (class "Default")
      (node (ref "R15") (pin "1") (pintype "passive"))
      (node (ref "TP16") (pin "1") (pinfunction "1_1") (pintype "passive"))
      (node (ref "U2") (pin "18") (pinfunction "HPO_L_18") (pintype "passive"))
    )
    (net (code "16") (name "/HPO_R") (class "Default")
      (node (ref "R16") (pin "1") (pintype "passive"))
      (node (ref "U2") (pin "19") (pinfunction "HPO_R_19") (pintype "passive"))
    )
    (net (code "17") (name "/HP_MIC") (class "Default")
      (node (ref "C137") (pin "2") (pinfunction "2_2") (pintype "passive"))
      (node (ref "FB12") (pin "2") (pinfunction "2_2") (pintype "passive"))
      (node (ref "J4") (pin "5") (pinfunction "SLEEVE_5") (pintype "passive"))
    )
    (net (code "18") (name "/I2C3_SCL") (class "Default")
      (node (ref "U2") (pin "39") (pinfunction "SCL_39") (pintype "passive"))
    )
    (net (code "19") (name "/I2C3_SDA") (class "Default")
      (node (ref "U2") (pin "40") (pinfunction "SDA_40") (pintype "passive"))
    )
    (net (code "20") (name "/IN1P_HP_MIC") (class "Default")
      (node (ref "C127") (pin "2") (pinfunction "2_2") (pintype "passive"))
      (node (ref "TP19") (pin "1") (pinfunction "1_1") (pintype "passive"))
      (node (ref "U2") (pin "11") (pinfunction "IN1P_RING2_11") (pintype "passive"))
    )
    (net (code "21") (name "/IRQ") (class "Default")
      (node (ref "R20") (pin "1") (pintype "passive"))
      (node (ref "U2") (pin "41") (pinfunction "GPIO1/IRQ_41") (pintype "passive"))
    )
    (net (code "22") (name "/J_DETECT") (class "Default")
      (node (ref "ESD10") (pin "2") (pinfunction "2_2") (pintype "passive"))
      (node (ref "J4") (pin "3") (pinfunction "SHUNT_A_3") (pintype "passive"))
      (node (ref "R18") (pin "2") (pintype "passive"))
      (node (ref "R181") (pin "1") (pintype "passive"))
      (node (ref "R5") (pin "1") (pintype "passive"))
      (node (ref "TP18") (pin "1") (pinfunction "1_1") (pintype "passive"))
    )
    (net (code "23") (name "/MCLK") (class "Default")
      (node (ref "R146") (pin "2") (pintype "passive"))
      (node (ref "R147") (pin "2") (pintype "passive"))
      (node (ref "U2") (pin "38") (pinfunction "MCLK_38") (pintype "passive"))
    )
    (net (code "24") (name "/MICBIAS1") (class "Default")
      (node (ref "C140") (pin "1") (pinfunction "1_1") (pintype "passive"))
      (node (ref "R23") (pin "2") (pintype "passive"))
      (node (ref "U2") (pin "13") (pinfunction "MICBIAS1_13") (pintype "passive"))
    )
    (net (code "25") (name "/OSC_CLK") (class "Default")
      (node (ref "C64") (pin "1") (pinfunction "1_1") (pintype "passive"))
      (node (ref "OSC1") (pin "3") (pinfunction "OUT_3") (pintype "output"))
      (node (ref "R146") (pin "1") (pintype "passive"))
    )
    (net (code "26") (name "/SAI2_MCLK") (class "Default") (node (ref "R147") (pin "1") (pintype "passive")))
    (net (code "28") (name "/SAI2_RXD") (class "Default")
      (node (ref "C3") (pin "1") (pinfunction "1_1") (pintype "passive"))
      (node (ref "U2") (pin "35") (pinfunction "ADCDAT1_35") (pintype "passive"))
    )
    (net (code "30") (name "/SAI2_TXC") (class "Default")
      (node (ref "C2") (pin "2") (pinfunction "2_2") (pintype "passive"))
      (node (ref "U2") (pin "37") (pinfunction "BCLK1_37") (pintype "passive"))
    )
    (net (code "31") (name "/SAI2_TXD") (class "Default")
      (node (ref "C1") (pin "2") (pinfunction "2_2") (pintype "passive"))
      (node (ref "U2") (pin "34") (pinfunction "DACDAT1_34") (pintype "passive"))
    )
    (net (code "32") (name "/SAI2_TXFS") (class "Default")
      (node (ref "C4") (pin "1") (pinfunction "1_1") (pintype "passive"))
      (node (ref "U2") (pin "36") (pinfunction "LRCK1_36") (pintype "passive"))
    )
    (net (code "33") (name "/SPDIF_RX") (class "Default")
      (node (ref "R181") (pin "2") (pintype "passive"))
      (node (ref "R20") (pin "2") (pintype "passive"))
    )
    (net (code "34") (name "/SPO_L_N") (class "Default")
      (node (ref "FB8") (pin "1") (pinfunction "1_1") (pintype "passive"))
      (node (ref "U2") (pin "48") (pinfunction "SPO_LN_48") (pintype "passive"))
    )
    (net (code "35") (name "/SPO_L_P") (class "Default")
      (node (ref "FB7") (pin "1") (pinfunction "1_1") (pintype "passive"))
      (node (ref "U2") (pin "1") (pinfunction "SPO_LP_1") (pintype "passive"))
    )
    (net (code "36") (name "/SPO_R_N") (class "Default")
      (node (ref "FB9") (pin "1") (pinfunction "1_1") (pintype "passive"))
      (node (ref "U2") (pin "44") (pinfunction "SPO_RN_44") (pintype "passive"))
    )
    (net (code "37") (name "/SPO_R_P") (class "Default")
      (node (ref "FB10") (pin "1") (pinfunction "1_1") (pintype "passive"))
      (node (ref "U2") (pin "45") (pinfunction "SPO_RP_45") (pintype "passive"))
    )
    (net (code "38") (name "AGND") (class "Default")
      (node (ref "C12") (pin "2") (pinfunction "2_2") (pintype "passive"))
      (node (ref "C135") (pin "1") (pinfunction "1_1") (pintype "passive"))
      (node (ref "C136") (pin "1") (pinfunction "1_1") (pintype "passive"))
      (node (ref "C137") (pin "1") (pinfunction "1_1") (pintype "passive"))
      (node (ref "C140") (pin "2") (pinfunction "2_2") (pintype "passive"))
      (node (ref "C24") (pin "1") (pinfunction "1_1") (pintype "passive"))
      (node (ref "C27") (pin "2") (pinfunction "2_2") (pintype "passive"))
      (node (ref "C28") (pin "2") (pinfunction "2_2") (pintype "passive"))
      (node (ref "C35") (pin "2") (pinfunction "2_2") (pintype "passive"))
      (node (ref "C36") (pin "2") (pinfunction "2_2") (pintype "passive"))
      (node (ref "C37") (pin "2") (pinfunction "2_2") (pintype "passive"))
      (node (ref "C38") (pin "2") (pinfunction "2_2") (pintype "passive"))
      (node (ref "C39") (pin "2") (pinfunction "2_2") (pintype "passive"))
      (node (ref "C6") (pin "2") (pinfunction "2_2") (pintype "passive"))
      (node (ref "C9") (pin "2") (pinfunction "2_2") (pintype "passive"))
      (node (ref "ESD10") (pin "1") (pinfunction "1_1") (pintype "passive"))
      (node (ref "ESD11") (pin "1") (pinfunction "1_1") (pintype "passive"))
      (node (ref "ESD9") (pin "1") (pinfunction "1_1") (pintype "passive"))
      (node (ref "J4") (pin "6") (pinfunction "RING_B_6") (pintype "passive"))
      (node (ref "R138") (pin "2") (pintype "passive"))
      (node (ref "R139") (pin "2") (pintype "passive"))
      (node (ref "R159") (pin "1") (pintype "passive"))
      (node (ref "R164") (pin "2") (pintype "passive"))
      (node (ref "R24") (pin "2") (pintype "passive"))
      (node (ref "U2") (pin "10") (pinfunction "AGND_10") (pintype "passive"))
      (node (ref "U2") (pin "17") (pinfunction "CPVREF_17") (pintype "passive"))
      (node (ref "U2") (pin "24") (pinfunction "CPGND_24") (pintype "passive"))
    )
    (net (code "39") (name "ANALOG_1v8") (class "Default")
      (node (ref "C35") (pin "1") (pinfunction "1_1") (pintype "passive"))
      (node (ref "C36") (pin "1") (pinfunction "1_1") (pintype "passive"))
      (node (ref "C37") (pin "1") (pinfunction "1_1") (pintype "passive"))
      (node (ref "C38") (pin "1") (pinfunction "1_1") (pintype "passive"))
      (node (ref "C39") (pin "1") (pinfunction "1_1") (pintype "passive"))
      (node (ref "C40") (pin "1") (pinfunction "1_1") (pintype "passive"))
      (node (ref "FB3") (pin "2") (pinfunction "2_2") (pintype "passive"))
      (node (ref "TP13") (pin "1") (pinfunction "1_1") (pintype "passive"))
      (node (ref "U2") (pin "21") (pinfunction "CPVDD_21") (pintype "passive"))
      (node (ref "U2") (pin "6") (pinfunction "AVDD_6") (pintype "passive"))
      (node (ref "U2") (pin "7") (pinfunction "DACREF_7") (pintype "passive"))
    )
    (net (code "40") (name "ANALOG_3v3") (class "Default")
      (node (ref "C32") (pin "1") (pinfunction "1_1") (pintype "passive"))
      (node (ref "FB2") (pin "2") (pinfunction "2_2") (pintype "passive"))
      (node (ref "R174") (pin "1") (pintype "passive"))
      (node (ref "TP12") (pin "1") (pinfunction "1_1") (pintype "passive"))
    )
    (net (code "41") (name "DBVDD") (class "Default")
      (node (ref "C11") (pin "1") (pinfunction "1_1") (pintype "passive"))
      (node (ref "C31") (pin "1") (pinfunction "1_1") (pintype "passive"))
      (node (ref "C44") (pin "1") (pinfunction "1_1") (pintype "passive"))
      (node (ref "C45") (pin "1") (pinfunction "1_1") (pintype "passive"))
      (node (ref "FB2") (pin "1") (pinfunction "1_1") (pintype "passive"))
      (node (ref "OSC1") (pin "1") (pinfunction "TRI_1") (pintype "passive"))
      (node (ref "OSC1") (pin "4") (pinfunction "VDD_4") (pintype "power_in"))
      (node (ref "R206") (pin "1") (pintype "passive"))
      (node (ref "R207") (pin "2") (pintype "passive"))
      (node (ref "R5") (pin "2") (pintype "passive"))
      (node (ref "U2") (pin "2") (pinfunction "DBVDD_2") (pintype "passive"))
      (node (ref "U4") (pin "2") (pinfunction "SELECT_2") (pintype "passive"))
    )
    (net (code "42") (name "DCDC_5V") (class "Default")
      (node (ref "C25") (pin "1") (pinfunction "1_1") (pintype "passive"))
      (node (ref "C26") (pin "1") (pinfunction "1_1") (pintype "passive"))
      (node (ref "U2") (pin "43") (pinfunction "SPKVDDR_43") (pintype "passive"))
      (node (ref "U2") (pin "47") (pinfunction "SPKVDDL_47") (pintype "passive"))
    )
    (net (code "43") (name "DCVDD") (class "Default")
      (node (ref "C41") (pin "1") (pinfunction "1_1") (pintype "passive"))
      (node (ref "U2") (pin "3") (pinfunction "DCVDD_3") (pintype "passive"))
    )
    (net (code "44") (name "GND") (class "Default")
      (node (ref "C1") (pin "1") (pinfunction "1_1") (pintype "passive"))
      (node (ref "C10") (pin "2") (pinfunction "2_2") (pintype "passive"))
      (node (ref "C11") (pin "2") (pinfunction "2_2") (pintype "passive"))
      (node (ref "C123") (pin "1") (pinfunction "1_1") (pintype "passive"))
      (node (ref "C124") (pin "1") (pinfunction "1_1") (pintype "passive"))
      (node (ref "C125") (pin "2") (pinfunction "2_2") (pintype "passive"))
      (node (ref "C126") (pin "2") (pinfunction "2_2") (pintype "passive"))
      (node (ref "C141") (pin "2") (pinfunction "2_2") (pintype "passive"))
      (node (ref "C142") (pin "2") (pinfunction "2_2") (pintype "passive"))
      (node (ref "C18") (pin "1") (pinfunction "1_1") (pintype "passive"))
      (node (ref "C19") (pin "1") (pinfunction "1_1") (pintype "passive"))
      (node (ref "C2") (pin "1") (pinfunction "1_1") (pintype "passive"))
      (node (ref "C20") (pin "2") (pinfunction "2_2") (pintype "passive"))
      (node (ref "C25") (pin "2") (pinfunction "2_2") (pintype "passive"))
      (node (ref "C26") (pin "2") (pinfunction "2_2") (pintype "passive"))
      (node (ref "C3") (pin "2") (pinfunction "2_2") (pintype "passive"))
      (node (ref "C30") (pin "2") (pinfunction "2_2") (pintype "passive"))
      (node (ref "C31") (pin "2") (pinfunction "2_2") (pintype "passive"))
      (node (ref "C32") (pin "2") (pinfunction "2_2") (pintype "passive"))
      (node (ref "C34") (pin "2") (pinfunction "2_2") (pintype "passive"))
      (node (ref "C4") (pin "2") (pinfunction "2_2") (pintype "passive"))
      (node (ref "C40") (pin "2") (pinfunction "2_2") (pintype "passive"))
      (node (ref "C41") (pin "2") (pinfunction "2_2") (pintype "passive"))
      (node (ref "C44") (pin "2") (pinfunction "2_2") (pintype "passive"))
      (node (ref "C45") (pin "2") (pinfunction "2_2") (pintype "passive"))
      (node (ref "C5") (pin "2") (pinfunction "2_2") (pintype "passive"))
      (node (ref "C64") (pin "2") (pinfunction "2_2") (pintype "passive"))
      (node (ref "ESD18") (pin "1") (pinfunction "1_1") (pintype "passive"))
      (node (ref "ESD19") (pin "1") (pinfunction "1_1") (pintype "passive"))
      (node (ref "ESD20") (pin "1") (pinfunction "1_1") (pintype "passive"))
      (node (ref "ESD21") (pin "1") (pinfunction "1_1") (pintype "passive"))
      (node (ref "OSC1") (pin "2") (pinfunction "GND_2") (pintype "passive"))
      (node (ref "R138") (pin "1") (pintype "passive"))
      (node (ref "R139") (pin "1") (pintype "passive"))
      (node (ref "R164") (pin "1") (pintype "passive"))
      (node (ref "R24") (pin "1") (pintype "passive"))
      (node (ref "R93") (pin "1") (pintype "passive"))
      (node (ref "U2") (pin "46") (pinfunction "SPKGND_46") (pintype "passive"))
      (node (ref "U2") (pin "49") (pinfunction "PAD/DGND_49") (pintype "passive"))
      (node (ref "U3") (pin "2") (pinfunction "SELECT_2") (pintype "passive"))
      (node (ref "U3") (pin "5") (pinfunction "GND_5") (pintype "power_in"))
      (node (ref "U3") (pin "6") (pinfunction "GND_6") (pintype "power_in"))
      (node (ref "U3") (pin "7") (pinfunction "GND_7") (pintype "power_in"))
      (node (ref "U3") (pin "8") (pinfunction "GND_8") (pintype "power_in"))
      (node (ref "U4") (pin "5") (pinfunction "GND_5") (pintype "power_in"))
      (node (ref "U4") (pin "6") (pinfunction "GND_6") (pintype "power_in"))
      (node (ref "U4") (pin "7") (pinfunction "GND_7") (pintype "power_in"))
      (node (ref "U4") (pin "8") (pinfunction "GND_8") (pintype "power_in"))
    )
    (net (code "45") (name "MICVDD") (class "Default")
      (node (ref "C27") (pin "1") (pinfunction "1_1") (pintype "passive"))
      (node (ref "C28") (pin "1") (pinfunction "1_1") (pintype "passive"))
      (node (ref "R174") (pin "2") (pintype "passive"))
      (node (ref "U2") (pin "15") (pinfunction "MICVDD_15") (pintype "passive"))
    )
    (net (code "46") (name "Net-(C127-Pad1)") (class "Default")
      (node (ref "C127") (pin "1") (pinfunction "1_1") (pintype "passive"))
      (node (ref "FB12") (pin "1") (pinfunction "1_1") (pintype "passive"))
      (node (ref "R159") (pin "2") (pintype "passive"))
      (node (ref "R23") (pin "1") (pintype "passive"))
    )
    (net (code "47") (name "Net-(J4-RING_A)") (class "Default")
      (node (ref "C136") (pin "2") (pinfunction "2_2") (pintype "passive"))
      (node (ref "ESD11") (pin "2") (pinfunction "2_2") (pintype "passive"))
      (node (ref "FB11") (pin "2") (pinfunction "2_2") (pintype "passive"))
      (node (ref "J4") (pin "1") (pinfunction "RING_A_1") (pintype "passive"))
      (node (ref "TP17") (pin "1") (pinfunction "1_1") (pintype "passive"))
    )
    (net (code "48") (name "Net-(J4-TIP_SPRING)") (class "Default")
      (node (ref "C135") (pin "2") (pinfunction "2_2") (pintype "passive"))
      (node (ref "ESD9") (pin "2") (pinfunction "2_2") (pintype "passive"))
      (node (ref "FB4") (pin "2") (pinfunction "2_2") (pintype "passive"))
      (node (ref "J4") (pin "4") (pinfunction "TIP_SPRING_4") (pintype "passive"))
    )
    (net (code "49") (name "Net-(U2-GPIO2{slash}DMIC_SCL)") (class "Default")
      (node (ref "R208") (pin "1") (pintype "passive"))
      (node (ref "U2") (pin "42") (pinfunction "GPIO2/DMIC_SCL_42") (pintype "passive"))
    )
    (net (code "50") (name "Net-(U2-JD1)") (class "Default")
      (node (ref "R18") (pin "1") (pintype "passive"))
      (node (ref "U2") (pin "16") (pinfunction "JD1_16") (pintype "passive"))
    )
    (net (code "51") (name "Net-(U2-MIC_CAP)") (class "Default")
      (node (ref "C24") (pin "2") (pinfunction "2_2") (pintype "passive"))
      (node (ref "U2") (pin "14") (pinfunction "MIC_CAP_14") (pintype "passive"))
    )
    (net (code "52") (name "Net-(U2-VREF)") (class "Default")
      (node (ref "C12") (pin "1") (pinfunction "1_1") (pintype "passive"))
      (node (ref "U2") (pin "8") (pinfunction "VREF_8") (pintype "passive"))
    )
    (net (code "53") (name "Net-(U3-DATA)") (class "Default")
      (node (ref "R210") (pin "2") (pintype "passive"))
      (node (ref "U3") (pin "4") (pinfunction "DATA_4") (pintype "passive"))
    )
    (net (code "54") (name "Net-(U3-VDD)") (class "Default")
      (node (ref "C141") (pin "1") (pinfunction "1_1") (pintype "passive"))
      (node (ref "C5") (pin "1") (pinfunction "1_1") (pintype "passive"))
      (node (ref "R206") (pin "2") (pintype "passive"))
      (node (ref "U3") (pin "1") (pinfunction "VDD_1") (pintype "power_in"))
    )
    (net (code "55") (name "Net-(U4-DATA)") (class "Default")
      (node (ref "R209") (pin "2") (pintype "passive"))
      (node (ref "U4") (pin "4") (pinfunction "DATA_4") (pintype "passive"))
    )
    (net (code "56") (name "Net-(U4-VDD)") (class "Default")
      (node (ref "C10") (pin "1") (pinfunction "1_1") (pintype "passive"))
      (node (ref "C142") (pin "1") (pinfunction "1_1") (pintype "passive"))
      (node (ref "R207") (pin "1") (pintype "passive"))
      (node (ref "U4") (pin "1") (pinfunction "VDD_1") (pintype "power_in"))
    )
    (net (code "57") (name "V1V8") (class "Default")
      (node (ref "C34") (pin "1") (pinfunction "1_1") (pintype "passive"))
      (node (ref "FB3") (pin "1") (pinfunction "1_1") (pintype "passive"))
    )
    (net (code "58") (name "unconnected-(J4-SHUNT_B-Pad2)") (class "Default")
      (node (ref "J4") (pin "2") (pinfunction "SHUNT_B_2") (pintype "passive+no_connect"))
    )
    (net (code "59") (name "unconnected-(U2-ADCDAT2-Pad33)") (class "Default")
      (node (ref "U2") (pin "33") (pinfunction "ADCDAT2_33") (pintype "passive+no_connect"))
    )
    (net (code "60") (name "unconnected-(U2-BCLK2-Pad31)") (class "Default")
      (node (ref "U2") (pin "31") (pinfunction "BCLK2_31") (pintype "passive+no_connect"))
    )
    (net (code "61") (name "unconnected-(U2-IN1N_SLEEVE-Pad12)") (class "Default")
      (node (ref "U2") (pin "12") (pinfunction "IN1N_SLEEVE_12") (pintype "passive+no_connect"))
    )
    (net (code "62") (name "unconnected-(U2-IN2N-Pad5)") (class "Default")
      (node (ref "U2") (pin "5") (pinfunction "IN2N_5") (pintype "passive+no_connect"))
    )
    (net (code "63") (name "unconnected-(U2-IN2P-Pad4)") (class "Default")
      (node (ref "U2") (pin "4") (pinfunction "IN2P_4") (pintype "passive+no_connect"))
    )
    (net (code "64") (name "unconnected-(U2-LOUT1L{slash}P-Pad28)") (class "Default")
      (node (ref "U2") (pin "28") (pinfunction "LOUT1L/P_28") (pintype "passive+no_connect"))
    )
    (net (code "65") (name "unconnected-(U2-LOUT1R{slash}N-Pad29)") (class "Default")
      (node (ref "U2") (pin "29") (pinfunction "LOUT1R/N_29") (pintype "passive+no_connect"))
    )
    (net (code "66") (name "unconnected-(U2-LRCK2-Pad30)") (class "Default")
      (node (ref "U2") (pin "30") (pinfunction "LRCK2_30") (pintype "passive+no_connect"))
    )
    (net (code "67") (name "unconnected-(U2-MICBIAS2-Pad9)") (class "Default")
      (node (ref "U2") (pin "9") (pinfunction "MICBIAS2_9") (pintype "passive+no_connect"))
    )
  )
)
